# sensor_board_v0_4.net
KiCad netlist of a schematic drawn in EAGLE
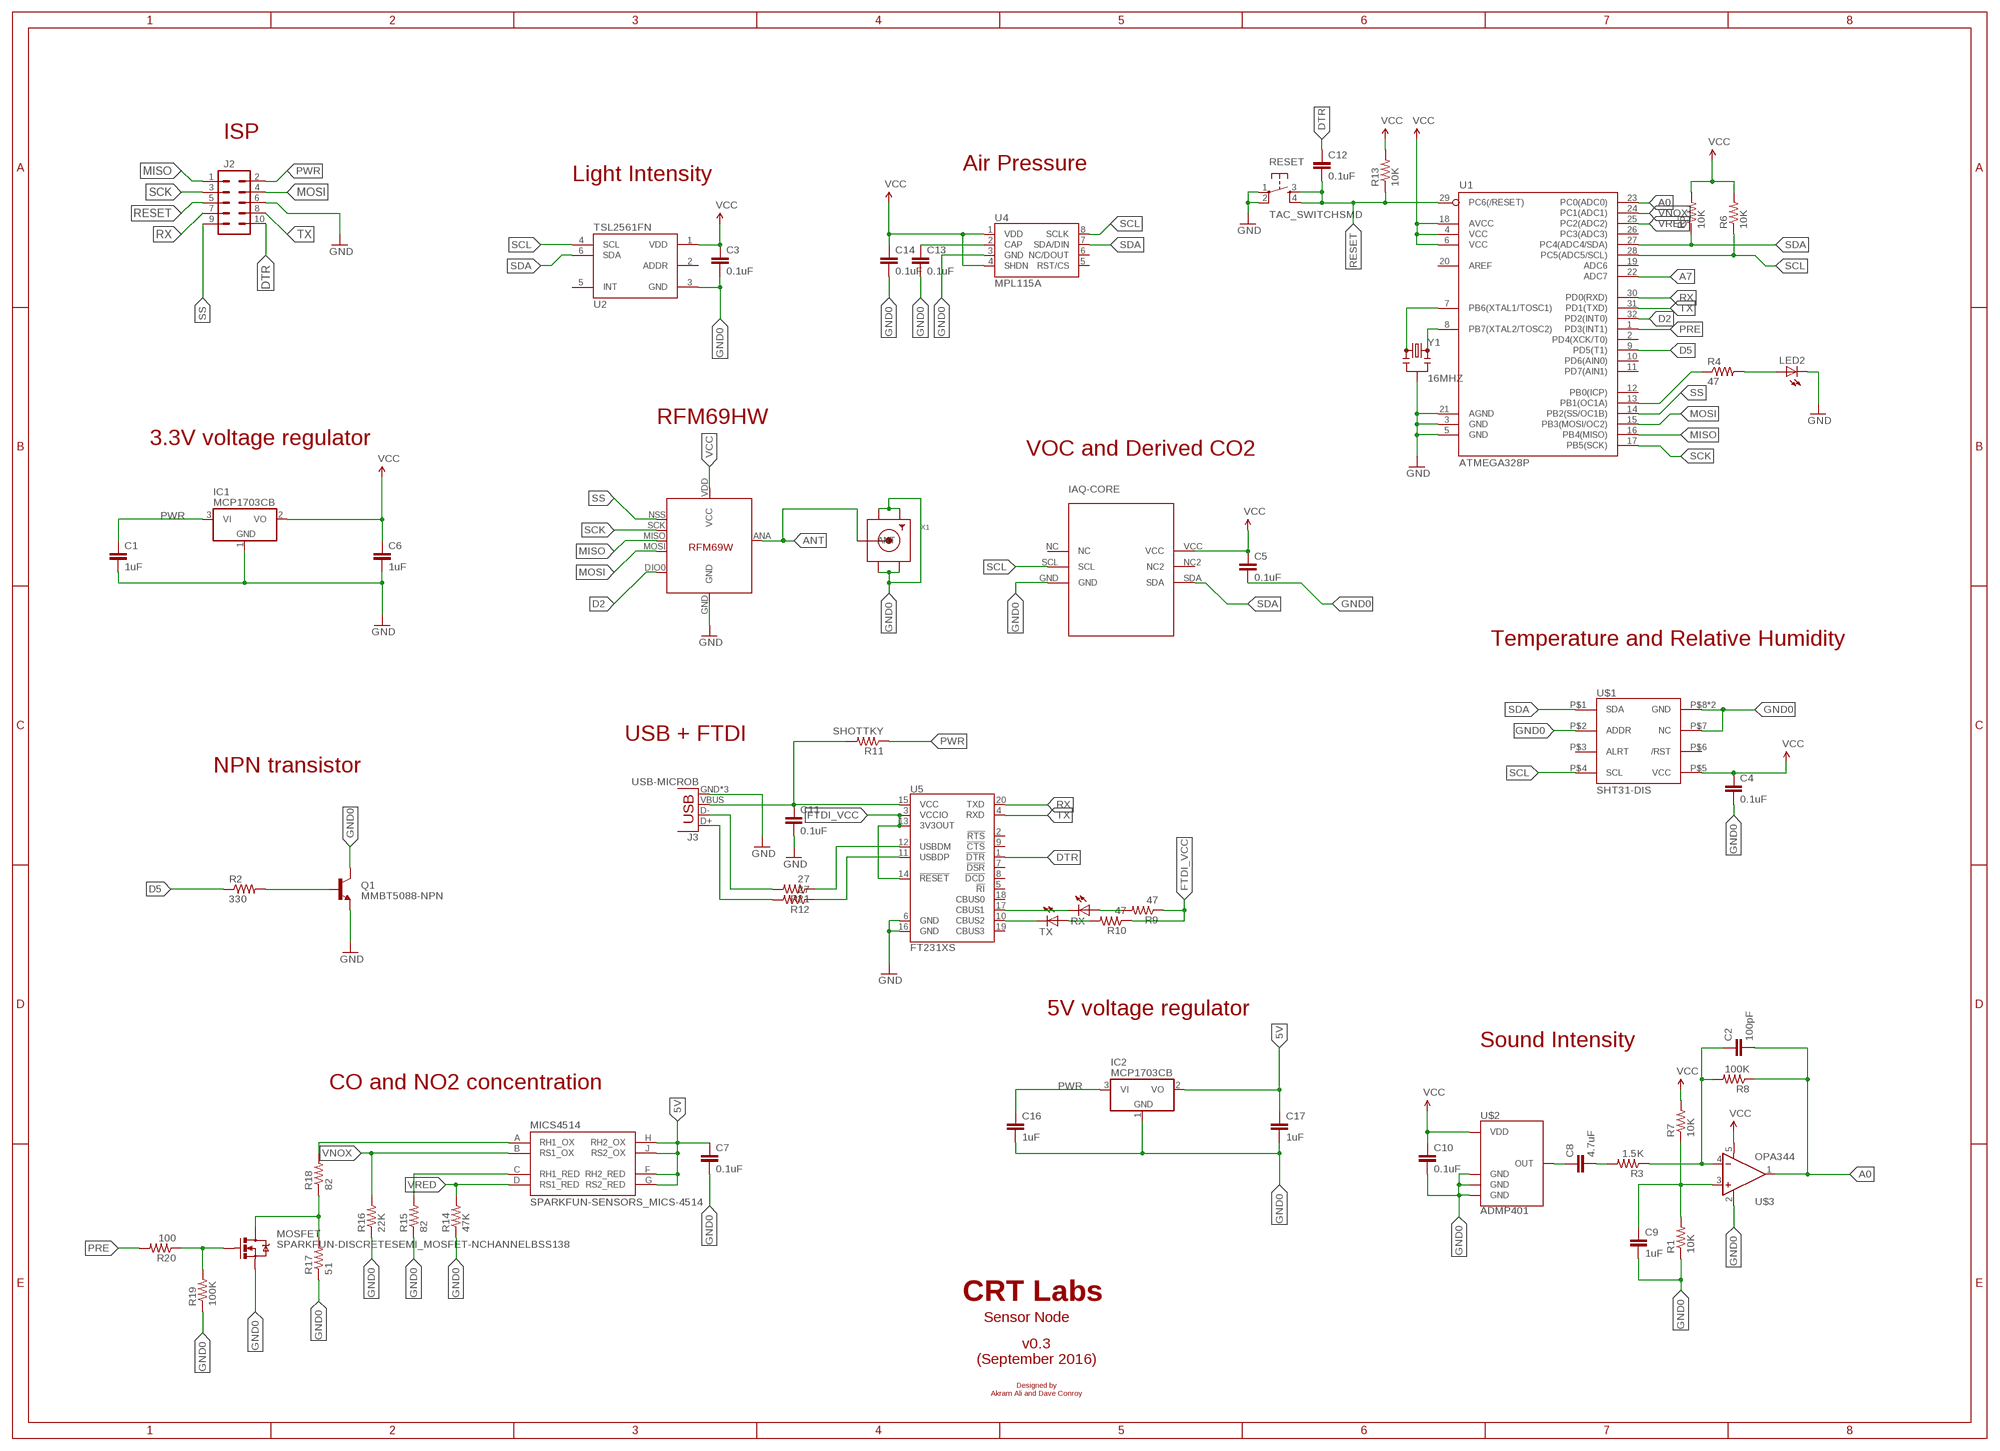
[diagram p0: schematic, sheet 1]

(export (version "E")
  (design (tool "Eeschema 10.0.6"))
  (components
    (comp (ref "C1")
      (value "1uF")
      (footprint "eagle-import:0805")
      (libsource (lib "eagle-import") (part "CAP0805"))
    )
    (comp (ref "C2")
      (value "100pF")
      (footprint "eagle-import:0805")
      (libsource (lib "eagle-import") (part "CAP0805"))
    )
    (comp (ref "C3")
      (value "0.1uF")
      (footprint "eagle-import:0805")
      (libsource (lib "eagle-import") (part "SparkFun-Passives_CAP0805"))
    )
    (comp (ref "C4")
      (value "0.1uF")
      (footprint "eagle-import:0805")
      (libsource (lib "eagle-import") (part "SparkFun-Passives_CAP0805"))
    )
    (comp (ref "C5")
      (value "0.1uF")
      (footprint "eagle-import:0805")
      (libsource (lib "eagle-import") (part "SparkFun-Passives_CAP0805"))
    )
    (comp (ref "C6")
      (value "1uF")
      (footprint "eagle-import:0805")
      (libsource (lib "eagle-import") (part "CAP0805"))
    )
    (comp (ref "C7")
      (value "0.1uF")
      (footprint "eagle-import:0805")
      (libsource (lib "eagle-import") (part "SparkFun-Passives_CAP0805"))
    )
    (comp (ref "C8")
      (value "4.7uF")
      (footprint "eagle-import:0805")
      (libsource (lib "eagle-import") (part "CAP0805"))
    )
    (comp (ref "C9")
      (value "1uF")
      (footprint "eagle-import:0805")
      (libsource (lib "eagle-import") (part "CAP0805"))
    )
    (comp (ref "C10")
      (value "0.1uF")
      (footprint "eagle-import:0805")
      (libsource (lib "eagle-import") (part "CAP0805"))
    )
    (comp (ref "C11")
      (value "0.1uF")
      (footprint "eagle-import:0805")
      (libsource (lib "eagle-import") (part "CAP0805"))
    )
    (comp (ref "C12")
      (value "0.1uF")
      (footprint "eagle-import:0805")
      (libsource (lib "eagle-import") (part "SparkFun-Passives_CAP0805"))
    )
    (comp (ref "C13")
      (value "0.1uF")
      (footprint "eagle-import:0805")
      (libsource (lib "eagle-import") (part "SparkFun-Passives_CAP0805"))
    )
    (comp (ref "C14")
      (value "0.1uF")
      (footprint "eagle-import:0805")
      (libsource (lib "eagle-import") (part "SparkFun-Passives_CAP0805"))
    )
    (comp (ref "C16")
      (value "1uF")
      (footprint "eagle-import:0805")
      (libsource (lib "eagle-import") (part "CAP0805"))
    )
    (comp (ref "C17")
      (value "1uF")
      (footprint "eagle-import:0805")
      (libsource (lib "eagle-import") (part "CAP0805"))
    )
    (comp (ref "IAQ-CORE")
      (value "IAQ-CORE")
      (footprint "eagle-import:IAQ-CORE")
      (fields (field (name "MPN") "IAQ CORE"))
      (libsource (lib "eagle-import") (part "IAQ-CORE"))
    )
    (comp (ref "IC1")
      (value "MCP1703CB")
      (footprint "eagle-import:SOT23")
      (fields (field (name "MPN") "MCP1703T-2502E/CB"))
      (libsource (lib "eagle-import") (part "MCP1703CB"))
    )
    (comp (ref "IC2")
      (value "MCP1703CB")
      (footprint "eagle-import:SOT23")
      (fields (field (name "MPN") "MCP1703T-2502E/CB"))
      (libsource (lib "eagle-import") (part "MCP1703CB"))
    )
    (comp (ref "J2")
      (value "M05X2PTH")
      (footprint "eagle-import:AVR_ICSP")
      (libsource (lib "eagle-import") (part "M05X2PTH"))
    )
    (comp (ref "J3")
      (value "USB-MICROB")
      (footprint "eagle-import:USB-MICROB")
      (libsource (lib "eagle-import") (part "USB-MICROB"))
    )
    (comp (ref "LED2")
      (value "LEDCHIPLED_0805")
      (footprint "eagle-import:CHIPLED_0805")
      (libsource (lib "eagle-import") (part "LEDCHIPLED_0805"))
    )
    (comp (ref "MICS4514")
      (value "SPARKFUN-SENSORS_MICS-4514")
      (footprint "eagle-import:SPARKFUN-SENSORS_MICS_10-SMD")
      (libsource (lib "eagle-import") (part "SPARKFUN-SENSORS_MICS-4514"))
    )
    (comp (ref "MOSFET")
      (value "SPARKFUN-DISCRETESEMI_MOSFET-NCHANNELBSS138")
      (footprint "eagle-import:SPARKFUN-DISCRETESEMI_SOT23-3")
      (libsource (lib "eagle-import") (part "SPARKFUN-DISCRETESEMI_MOSFET-NCHANNELBSS138"))
    )
    (comp (ref "Q1")
      (value "MMBT5088-NPN")
      (footprint "eagle-import:SOT23-3")
      (libsource (lib "eagle-import") (part "TRANSISTOR_NPNMMBT5088"))
    )
    (comp (ref "R1")
      (value "10K")
      (footprint "eagle-import:0805")
      (libsource (lib "eagle-import") (part "RESISTOR0805-RES"))
    )
    (comp (ref "R2")
      (value "330")
      (footprint "eagle-import:0805")
      (libsource (lib "eagle-import") (part "RESISTOR0805-RES"))
    )
    (comp (ref "R3")
      (value "1.5K")
      (footprint "eagle-import:0805")
      (libsource (lib "eagle-import") (part "RESISTOR0805-RES"))
    )
    (comp (ref "R4")
      (value "47")
      (footprint "eagle-import:0805")
      (libsource (lib "eagle-import") (part "SparkFun-Resistors_RESISTOR0805-RES"))
    )
    (comp (ref "R5")
      (value "10K")
      (footprint "eagle-import:0805")
      (libsource (lib "eagle-import") (part "SparkFun-Resistors_RESISTOR0805-RES"))
    )
    (comp (ref "R6")
      (value "10K")
      (footprint "eagle-import:0805")
      (libsource (lib "eagle-import") (part "SparkFun-Resistors_RESISTOR0805-RES"))
    )
    (comp (ref "R7")
      (value "10K")
      (footprint "eagle-import:0805")
      (libsource (lib "eagle-import") (part "RESISTOR0805-RES"))
    )
    (comp (ref "R8")
      (value "100K")
      (footprint "eagle-import:0805")
      (libsource (lib "eagle-import") (part "RESISTOR0805-RES"))
    )
    (comp (ref "R9")
      (value "47")
      (footprint "eagle-import:0805")
      (libsource (lib "eagle-import") (part "RESISTOR0805-RES"))
    )
    (comp (ref "R10")
      (value "47")
      (footprint "eagle-import:0805")
      (libsource (lib "eagle-import") (part "RESISTOR0805-RES"))
    )
    (comp (ref "R11")
      (value "SHOTTKY")
      (footprint "eagle-import:0805")
      (libsource (lib "eagle-import") (part "RESISTOR0805-RES"))
    )
    (comp (ref "R12")
      (value "27")
      (footprint "eagle-import:0805")
      (libsource (lib "eagle-import") (part "RESISTOR0805-RES"))
    )
    (comp (ref "R13")
      (value "10K")
      (footprint "eagle-import:0805")
      (libsource (lib "eagle-import") (part "RESISTOR0805-RES"))
    )
    (comp (ref "R14")
      (value "47K")
      (footprint "eagle-import:0805")
      (libsource (lib "eagle-import") (part "RESISTOR0805-RES"))
    )
    (comp (ref "R15")
      (value "82")
      (footprint "eagle-import:0805")
      (libsource (lib "eagle-import") (part "RESISTOR0805-RES"))
    )
    (comp (ref "R16")
      (value "22K")
      (footprint "eagle-import:0805")
      (libsource (lib "eagle-import") (part "RESISTOR0805-RES"))
    )
    (comp (ref "R17")
      (value "51")
      (footprint "eagle-import:0805")
      (libsource (lib "eagle-import") (part "RESISTOR0805-RES"))
    )
    (comp (ref "R18")
      (value "82")
      (footprint "eagle-import:0805")
      (libsource (lib "eagle-import") (part "RESISTOR0805-RES"))
    )
    (comp (ref "R19")
      (value "100K")
      (footprint "eagle-import:0805")
      (libsource (lib "eagle-import") (part "RESISTOR0805-RES"))
    )
    (comp (ref "R20")
      (value "100")
      (footprint "eagle-import:0805")
      (libsource (lib "eagle-import") (part "RESISTOR0805-RES"))
    )
    (comp (ref "R21")
      (value "27")
      (footprint "eagle-import:0805")
      (libsource (lib "eagle-import") (part "RESISTOR0805-RES"))
    )
    (comp (ref "RESET")
      (value "TAC_SWITCHSMD")
      (footprint "eagle-import:TACTILE-SWITCH-SMD")
      (libsource (lib "eagle-import") (part "TAC_SWITCHSMD"))
    )
    (comp (ref "RX")
      (value "LEDCHIPLED_0805")
      (footprint "eagle-import:CHIPLED_0805")
      (libsource (lib "eagle-import") (part "LEDCHIPLED_0805"))
    )
    (comp (ref "TX")
      (value "LEDCHIPLED_0805")
      (footprint "eagle-import:CHIPLED_0805")
      (libsource (lib "eagle-import") (part "LEDCHIPLED_0805"))
    )
    (comp (ref "U$1")
      (value "SHT31-DIS")
      (footprint "eagle-import:SHT3X")
      (fields (field (name "MPN") "SHT31-DIS-B"))
      (libsource (lib "eagle-import") (part "SHT31-DIS"))
    )
    (comp (ref "U$2")
      (value "ADMP401")
      (footprint "eagle-import:ADMP401")
      (libsource (lib "eagle-import") (part "ADMP401"))
    )
    (comp (ref "U$3")
      (value "OPA344")
      (footprint "eagle-import:SOT23-5")
      (libsource (lib "eagle-import") (part "OPA344"))
    )
    (comp (ref "U$4")
      (value "RFM69HW")
      (footprint "eagle-import:LOWPOWERLAB_RFM69W-MINPADS")
      (libsource (lib "eagle-import") (part "LOWPOWERLAB_RFM69"))
    )
    (comp (ref "U1")
      (value "ATMEGA328P")
      (footprint "eagle-import:TQFP32-08")
      (fields (field (name "MPN") "ATMEGA328PB-AU"))
      (libsource (lib "eagle-import") (part "ATMEGA328P_TQFP"))
    )
    (comp (ref "U2")
      (value "TSL2561FN")
      (footprint "eagle-import:FN-6")
      (fields (field (name "MANF") "AMS-TAOS-USA-Inc."))
      (libsource (lib "eagle-import") (part "TSL2561FN"))
    )
    (comp (ref "U4")
      (value "MPL115A")
      (footprint "eagle-import:LGA8")
      (libsource (lib "eagle-import") (part "MPL115A"))
    )
    (comp (ref "U5")
      (value "FT231XS")
      (footprint "eagle-import:SSOP20_L")
      (libsource (lib "eagle-import") (part "FT231XS"))
    )
    (comp (ref "X1")
      (value "SMACONNECTOR_EDGE")
      (footprint "eagle-import:SMA_EDGELAUNCH")
      (libsource (lib "eagle-import") (part "SMACONNECTOR_EDGE"))
    )
    (comp (ref "Y1")
      (value "16MHZ")
      (footprint "eagle-import:RESONATOR-SMD")
      (libsource (lib "eagle-import") (part "RESONATOR16MHZ"))
    )
  )
  (nets
    (net (code "1") (name "5V") (class "Default")
      (node (ref "C17") (pin "1") (pinfunction "1_1") (pintype "passive"))
      (node (ref "C7") (pin "1") (pinfunction "1_1") (pintype "passive"))
      (node (ref "IC2") (pin "2") (pinfunction "VO_2") (pintype "passive"))
      (node (ref "MICS4514") (pin "F") (pinfunction "RH2_RED_F") (pintype "bidirectional"))
      (node (ref "MICS4514") (pin "G") (pinfunction "RS2_RED_G") (pintype "bidirectional"))
      (node (ref "MICS4514") (pin "H") (pinfunction "RH2_OX_H") (pintype "bidirectional"))
      (node (ref "MICS4514") (pin "J") (pinfunction "RS2_OX_J") (pintype "bidirectional"))
    )
    (net (code "2") (name "A0") (class "Default")
      (node (ref "C2") (pin "2") (pinfunction "2_2") (pintype "passive"))
      (node (ref "R8") (pin "1") (pinfunction "1_1") (pintype "passive"))
      (node (ref "U$3") (pin "1") (pinfunction "OUT_1") (pintype "output"))
      (node (ref "U1") (pin "23") (pinfunction "PC0(ADC0)_23") (pintype "bidirectional"))
    )
    (net (code "3") (name "A7") (class "Default")
      (node (ref "U1") (pin "22") (pinfunction "ADC7_22") (pintype "bidirectional"))
    )
    (net (code "4") (name "ANT") (class "Default")
      (node (ref "U$4") (pin "ANA") (pinfunction "ANT_ANA") (pintype "passive"))
      (node (ref "X1") (pin "P") (pinfunction "ANT_P") (pintype "bidirectional"))
    )
    (net (code "5") (name "D2") (class "Default")
      (node (ref "U$4") (pin "DIO0") (pinfunction "DIO0_DIO0") (pintype "open_collector"))
      (node (ref "U1") (pin "32") (pinfunction "PD2(INT0)_32") (pintype "bidirectional"))
    )
    (net (code "6") (name "D5") (class "Default")
      (node (ref "R2") (pin "1") (pinfunction "1_1") (pintype "passive"))
      (node (ref "U1") (pin "9") (pinfunction "PD5(T1)_9") (pintype "bidirectional"))
    )
    (net (code "7") (name "DTR") (class "Default")
      (node (ref "C12") (pin "1") (pinfunction "1_1") (pintype "passive"))
      (node (ref "J2") (pin "10") (pinfunction "10_10") (pintype "passive"))
      (node (ref "U5") (pin "1") (pinfunction "~{DTR}_1") (pintype "bidirectional"))
    )
    (net (code "8") (name "FTDI_VCC") (class "Default")
      (node (ref "R10") (pin "1") (pinfunction "1_1") (pintype "passive"))
      (node (ref "R9") (pin "1") (pinfunction "1_1") (pintype "passive"))
      (node (ref "U5") (pin "13") (pinfunction "3V3OUT_13") (pintype "bidirectional"))
      (node (ref "U5") (pin "14") (pinfunction "~{RESET}_14") (pintype "bidirectional"))
      (node (ref "U5") (pin "3") (pinfunction "VCCIO_3") (pintype "bidirectional"))
    )
    (net (code "9") (name "GND") (class "Default")
      (node (ref "C1") (pin "2") (pinfunction "2_2") (pintype "passive"))
      (node (ref "C11") (pin "2") (pinfunction "2_2") (pintype "passive"))
      (node (ref "C6") (pin "2") (pinfunction "2_2") (pintype "passive"))
      (node (ref "IC1") (pin "1") (pinfunction "GND_1") (pintype "passive"))
      (node (ref "J2") (pin "6") (pinfunction "6_6") (pintype "passive"))
      (node (ref "J3") (pin "GND") (pinfunction "GND_GND") (pintype "bidirectional"))
      (node (ref "J3") (pin "MT1") (pinfunction "GND_MT1") (pintype "bidirectional"))
      (node (ref "J3") (pin "MT2") (pinfunction "GND_MT2") (pintype "bidirectional"))
      (node (ref "LED2") (pin "C") (pinfunction "C_C") (pintype "passive"))
      (node (ref "Q1") (pin "2") (pinfunction "E_2") (pintype "passive"))
      (node (ref "RESET") (pin "1") (pinfunction "1_1") (pintype "passive"))
      (node (ref "RESET") (pin "2") (pinfunction "2_2") (pintype "passive"))
      (node (ref "U$4") (pin "GND") (pinfunction "GND_GND") (pintype "power_in"))
      (node (ref "U1") (pin "21") (pinfunction "AGND_21") (pintype "bidirectional"))
      (node (ref "U1") (pin "3") (pinfunction "GND_3") (pintype "bidirectional"))
      (node (ref "U1") (pin "5") (pinfunction "GND_5") (pintype "bidirectional"))
      (node (ref "U5") (pin "16") (pinfunction "GND_16") (pintype "bidirectional"))
      (node (ref "U5") (pin "6") (pinfunction "GND_6") (pintype "bidirectional"))
      (node (ref "Y1") (pin "2") (pinfunction "2_2") (pintype "passive"))
    )
    (net (code "10") (name "GND0") (class "Default")
      (node (ref "C10") (pin "2") (pinfunction "2_2") (pintype "passive"))
      (node (ref "C13") (pin "2") (pinfunction "2_2") (pintype "passive"))
      (node (ref "C14") (pin "2") (pinfunction "2_2") (pintype "passive"))
      (node (ref "C16") (pin "2") (pinfunction "2_2") (pintype "passive"))
      (node (ref "C17") (pin "2") (pinfunction "2_2") (pintype "passive"))
      (node (ref "C3") (pin "2") (pinfunction "2_2") (pintype "passive"))
      (node (ref "C4") (pin "2") (pinfunction "2_2") (pintype "passive"))
      (node (ref "C5") (pin "2") (pinfunction "2_2") (pintype "passive"))
      (node (ref "C7") (pin "2") (pinfunction "2_2") (pintype "passive"))
      (node (ref "C9") (pin "2") (pinfunction "2_2") (pintype "passive"))
      (node (ref "IAQ-CORE") (pin "GND") (pinfunction "GND_GND") (pintype "bidirectional"))
      (node (ref "IC2") (pin "1") (pinfunction "GND_1") (pintype "passive"))
      (node (ref "MOSFET") (pin "2") (pinfunction "S_2") (pintype "passive"))
      (node (ref "Q1") (pin "3") (pinfunction "C_3") (pintype "passive"))
      (node (ref "R1") (pin "1") (pinfunction "1_1") (pintype "passive"))
      (node (ref "R14") (pin "1") (pinfunction "1_1") (pintype "passive"))
      (node (ref "R15") (pin "1") (pinfunction "1_1") (pintype "passive"))
      (node (ref "R16") (pin "1") (pinfunction "1_1") (pintype "passive"))
      (node (ref "R17") (pin "1") (pinfunction "1_1") (pintype "passive"))
      (node (ref "R19") (pin "1") (pinfunction "1_1") (pintype "passive"))
      (node (ref "U$1") (pin "P$2") (pinfunction "ADDR_P$2") (pintype "bidirectional"))
      (node (ref "U$1") (pin "P$7") (pinfunction "NC_P$7") (pintype "bidirectional"))
      (node (ref "U$1") (pin "P$8") (pinfunction "GND_P$8") (pintype "bidirectional"))
      (node (ref "U$1") (pin "PAD") (pinfunction "GND_PAD") (pintype "bidirectional"))
      (node (ref "U$2") (pin "2") (pinfunction "GND_2") (pintype "bidirectional"))
      (node (ref "U$2") (pin "4") (pinfunction "GND_4") (pintype "bidirectional"))
      (node (ref "U$2") (pin "6") (pinfunction "GND_6") (pintype "bidirectional"))
      (node (ref "U$3") (pin "2") (pinfunction "V-_2") (pintype "power_in"))
      (node (ref "U2") (pin "3") (pinfunction "GND_3") (pintype "power_in"))
      (node (ref "U4") (pin "3") (pinfunction "GND_3") (pintype "bidirectional"))
      (node (ref "X1") (pin "GND@1") (pinfunction "GND4_GND@1") (pintype "power_in"))
      (node (ref "X1") (pin "GND@2") (pinfunction "GND3_GND@2") (pintype "power_in"))
      (node (ref "X1") (pin "GND@3") (pinfunction "GND2_GND@3") (pintype "power_in"))
      (node (ref "X1") (pin "GND@4") (pinfunction "GND1_GND@4") (pintype "power_in"))
    )
    (net (code "11") (name "MISO") (class "Default")
      (node (ref "J2") (pin "1") (pinfunction "1_1") (pintype "passive"))
      (node (ref "U$4") (pin "MISO") (pinfunction "MISO_MISO") (pintype "input"))
      (node (ref "U1") (pin "16") (pinfunction "PB4(MISO)_16") (pintype "bidirectional"))
    )
    (net (code "12") (name "MOSI") (class "Default")
      (node (ref "J2") (pin "4") (pinfunction "4_4") (pintype "passive"))
      (node (ref "U$4") (pin "MOSI") (pinfunction "MOSI_MOSI") (pintype "output"))
      (node (ref "U1") (pin "15") (pinfunction "PB3(MOSI/OC2)_15") (pintype "bidirectional"))
    )
    (net (code "13") (name "Net-(C8-Pad2)") (class "Default")
      (node (ref "C8") (pin "2") (pinfunction "2_2") (pintype "passive"))
      (node (ref "R3") (pin "2") (pinfunction "2_2") (pintype "passive"))
    )
    (net (code "14") (name "Net-(J3-PadD+)") (class "Default")
      (node (ref "J3") (pin "D+") (pinfunction "D+_D+") (pintype "bidirectional"))
      (node (ref "R12") (pin "2") (pinfunction "2_2") (pintype "passive"))
    )
    (net (code "15") (name "Net-(J3-PadD-)") (class "Default")
      (node (ref "J3") (pin "D-") (pinfunction "D-_D-") (pintype "bidirectional"))
      (node (ref "R21") (pin "2") (pinfunction "2_2") (pintype "passive"))
    )
    (net (code "16") (name "Net-(LED2-PadA)") (class "Default")
      (node (ref "LED2") (pin "A") (pinfunction "A_A") (pintype "passive"))
      (node (ref "R4") (pin "2") (pinfunction "2_2") (pintype "passive"))
    )
    (net (code "17") (name "Net-(MICS4514-RH1_OX)") (class "Default")
      (node (ref "MICS4514") (pin "A") (pinfunction "RH1_OX_A") (pintype "bidirectional"))
      (node (ref "R18") (pin "2") (pinfunction "2_2") (pintype "passive"))
    )
    (net (code "18") (name "Net-(MICS4514-RH1_RED)") (class "Default")
      (node (ref "MICS4514") (pin "C") (pinfunction "RH1_RED_C") (pintype "bidirectional"))
      (node (ref "R15") (pin "2") (pinfunction "2_2") (pintype "passive"))
    )
    (net (code "19") (name "Net-(MOSFET-D)") (class "Default")
      (node (ref "MOSFET") (pin "3") (pinfunction "D_3") (pintype "passive"))
      (node (ref "R17") (pin "2") (pinfunction "2_2") (pintype "passive"))
      (node (ref "R18") (pin "1") (pinfunction "1_1") (pintype "passive"))
    )
    (net (code "20") (name "Net-(MOSFET-G)") (class "Default")
      (node (ref "MOSFET") (pin "1") (pinfunction "G_1") (pintype "passive"))
      (node (ref "R19") (pin "2") (pinfunction "2_2") (pintype "passive"))
      (node (ref "R20") (pin "1") (pinfunction "1_1") (pintype "passive"))
    )
    (net (code "21") (name "Net-(Q1-B)") (class "Default")
      (node (ref "Q1") (pin "1") (pinfunction "B_1") (pintype "passive"))
      (node (ref "R2") (pin "2") (pinfunction "2_2") (pintype "passive"))
    )
    (net (code "22") (name "Net-(R9-Pad2)") (class "Default")
      (node (ref "R9") (pin "2") (pinfunction "2_2") (pintype "passive"))
      (node (ref "RX") (pin "A") (pinfunction "A_A") (pintype "passive"))
    )
    (net (code "23") (name "Net-(R10-Pad2)") (class "Default")
      (node (ref "R10") (pin "2") (pinfunction "2_2") (pintype "passive"))
      (node (ref "TX") (pin "A") (pinfunction "A_A") (pintype "passive"))
    )
    (net (code "24") (name "Net-(U$2-OUT)") (class "Default")
      (node (ref "C8") (pin "1") (pinfunction "1_1") (pintype "passive"))
      (node (ref "U$2") (pin "1") (pinfunction "OUT_1") (pintype "bidirectional"))
    )
    (net (code "25") (name "Net-(U$3-+IN)") (class "Default")
      (node (ref "C9") (pin "1") (pinfunction "1_1") (pintype "passive"))
      (node (ref "R1") (pin "2") (pinfunction "2_2") (pintype "passive"))
      (node (ref "R7") (pin "1") (pinfunction "1_1") (pintype "passive"))
      (node (ref "U$3") (pin "3") (pinfunction "+IN_3") (pintype "input"))
    )
    (net (code "26") (name "Net-(U$3--IN)") (class "Default")
      (node (ref "C2") (pin "1") (pinfunction "1_1") (pintype "passive"))
      (node (ref "R3") (pin "1") (pinfunction "1_1") (pintype "passive"))
      (node (ref "R8") (pin "2") (pinfunction "2_2") (pintype "passive"))
      (node (ref "U$3") (pin "4") (pinfunction "-IN_4") (pintype "input"))
    )
    (net (code "27") (name "Net-(U1-PB1(OC1A))") (class "Default")
      (node (ref "R4") (pin "1") (pinfunction "1_1") (pintype "passive"))
      (node (ref "U1") (pin "13") (pinfunction "PB1(OC1A)_13") (pintype "bidirectional"))
    )
    (net (code "28") (name "Net-(U1-PB6(XTAL1{slash}TOSC1))") (class "Default")
      (node (ref "U1") (pin "7") (pinfunction "PB6(XTAL1/TOSC1)_7") (pintype "bidirectional"))
      (node (ref "Y1") (pin "1") (pinfunction "1_1") (pintype "passive"))
    )
    (net (code "29") (name "Net-(U1-PB7(XTAL2{slash}TOSC2))") (class "Default")
      (node (ref "U1") (pin "8") (pinfunction "PB7(XTAL2/TOSC2)_8") (pintype "bidirectional"))
      (node (ref "Y1") (pin "3") (pinfunction "3_3") (pintype "passive"))
    )
    (net (code "30") (name "Net-(U4-CAP)") (class "Default")
      (node (ref "C13") (pin "1") (pinfunction "1_1") (pintype "passive"))
      (node (ref "U4") (pin "2") (pinfunction "CAP_2") (pintype "bidirectional"))
    )
    (net (code "31") (name "Net-(U5-CBUS1)") (class "Default")
      (node (ref "RX") (pin "C") (pinfunction "C_C") (pintype "passive"))
      (node (ref "U5") (pin "17") (pinfunction "CBUS1_17") (pintype "bidirectional"))
    )
    (net (code "32") (name "Net-(U5-CBUS2)") (class "Default")
      (node (ref "TX") (pin "C") (pinfunction "C_C") (pintype "passive"))
      (node (ref "U5") (pin "10") (pinfunction "CBUS2_10") (pintype "bidirectional"))
    )
    (net (code "33") (name "Net-(U5-USBDM)") (class "Default")
      (node (ref "R21") (pin "1") (pinfunction "1_1") (pintype "passive"))
      (node (ref "U5") (pin "12") (pinfunction "USBDM_12") (pintype "bidirectional"))
    )
    (net (code "34") (name "Net-(U5-USBDP)") (class "Default")
      (node (ref "R12") (pin "1") (pinfunction "1_1") (pintype "passive"))
      (node (ref "U5") (pin "11") (pinfunction "USBDP_11") (pintype "bidirectional"))
    )
    (net (code "35") (name "Net-(U5-VCC)") (class "Default")
      (node (ref "C11") (pin "1") (pinfunction "1_1") (pintype "passive"))
      (node (ref "J3") (pin "VBUS") (pinfunction "VBUS_VBUS") (pintype "bidirectional"))
      (node (ref "R11") (pin "2") (pinfunction "2_2") (pintype "passive"))
      (node (ref "U5") (pin "15") (pinfunction "VCC_15") (pintype "bidirectional"))
    )
    (net (code "36") (name "PRE") (class "Default")
      (node (ref "R20") (pin "2") (pinfunction "2_2") (pintype "passive"))
      (node (ref "U1") (pin "1") (pinfunction "PD3(INT1)_1") (pintype "bidirectional"))
    )
    (net (code "37") (name "PWR") (class "Default")
      (node (ref "C1") (pin "1") (pinfunction "1_1") (pintype "passive"))
      (node (ref "C16") (pin "1") (pinfunction "1_1") (pintype "passive"))
      (node (ref "IC1") (pin "3") (pinfunction "VI_3") (pintype "input"))
      (node (ref "IC2") (pin "3") (pinfunction "VI_3") (pintype "input"))
      (node (ref "J2") (pin "2") (pinfunction "2_2") (pintype "passive"))
      (node (ref "R11") (pin "1") (pinfunction "1_1") (pintype "passive"))
    )
    (net (code "38") (name "RESET") (class "Default")
      (node (ref "C12") (pin "2") (pinfunction "2_2") (pintype "passive"))
      (node (ref "J2") (pin "5") (pinfunction "5_5") (pintype "passive"))
      (node (ref "R13") (pin "1") (pinfunction "1_1") (pintype "passive"))
      (node (ref "RESET") (pin "3") (pinfunction "3_3") (pintype "passive"))
      (node (ref "RESET") (pin "4") (pinfunction "4_4") (pintype "passive"))
      (node (ref "U1") (pin "29") (pinfunction "PC6(/RESET)_29") (pintype "bidirectional"))
    )
    (net (code "39") (name "RX") (class "Default")
      (node (ref "J2") (pin "7") (pinfunction "7_7") (pintype "passive"))
      (node (ref "U1") (pin "30") (pinfunction "PD0(RXD)_30") (pintype "bidirectional"))
      (node (ref "U5") (pin "20") (pinfunction "TXD_20") (pintype "bidirectional"))
    )
    (net (code "40") (name "SCK") (class "Default")
      (node (ref "J2") (pin "3") (pinfunction "3_3") (pintype "passive"))
      (node (ref "U$4") (pin "SCK") (pinfunction "SCK_SCK") (pintype "input"))
      (node (ref "U1") (pin "17") (pinfunction "PB5(SCK)_17") (pintype "bidirectional"))
    )
    (net (code "41") (name "SCL") (class "Default")
      (node (ref "IAQ-CORE") (pin "SCL") (pinfunction "SCL_SCL") (pintype "bidirectional"))
      (node (ref "R6") (pin "1") (pinfunction "1_1") (pintype "passive"))
      (node (ref "U$1") (pin "P$4") (pinfunction "SCL_P$4") (pintype "bidirectional"))
      (node (ref "U1") (pin "28") (pinfunction "PC5(ADC5/SCL)_28") (pintype "bidirectional"))
      (node (ref "U2") (pin "4") (pinfunction "SCL_4") (pintype "input"))
      (node (ref "U4") (pin "8") (pinfunction "SCLK_8") (pintype "bidirectional"))
    )
    (net (code "42") (name "SDA") (class "Default")
      (node (ref "IAQ-CORE") (pin "SDA") (pinfunction "SDA_SDA") (pintype "bidirectional"))
      (node (ref "R5") (pin "1") (pinfunction "1_1") (pintype "passive"))
      (node (ref "U$1") (pin "P$1") (pinfunction "SDA_P$1") (pintype "bidirectional"))
      (node (ref "U1") (pin "27") (pinfunction "PC4(ADC4/SDA)_27") (pintype "bidirectional"))
      (node (ref "U2") (pin "6") (pinfunction "SDA_6") (pintype "bidirectional"))
      (node (ref "U4") (pin "7") (pinfunction "SDA/DIN_7") (pintype "bidirectional"))
    )
    (net (code "43") (name "SS") (class "Default")
      (node (ref "J2") (pin "9") (pinfunction "9_9") (pintype "passive"))
      (node (ref "U$4") (pin "NSS") (pinfunction "SEL_NSS") (pintype "input"))
      (node (ref "U1") (pin "14") (pinfunction "PB2(SS/OC1B)_14") (pintype "bidirectional"))
    )
    (net (code "44") (name "TX") (class "Default")
      (node (ref "J2") (pin "8") (pinfunction "8_8") (pintype "passive"))
      (node (ref "U1") (pin "31") (pinfunction "PD1(TXD)_31") (pintype "bidirectional"))
      (node (ref "U5") (pin "4") (pinfunction "RXD_4") (pintype "bidirectional"))
    )
    (net (code "45") (name "VCC") (class "Default")
      (node (ref "C10") (pin "1") (pinfunction "1_1") (pintype "passive"))
      (node (ref "C14") (pin "1") (pinfunction "1_1") (pintype "passive"))
      (node (ref "C3") (pin "1") (pinfunction "1_1") (pintype "passive"))
      (node (ref "C4") (pin "1") (pinfunction "1_1") (pintype "passive"))
      (node (ref "C5") (pin "1") (pinfunction "1_1") (pintype "passive"))
      (node (ref "C6") (pin "1") (pinfunction "1_1") (pintype "passive"))
      (node (ref "IAQ-CORE") (pin "VCC") (pinfunction "VCC_VCC") (pintype "bidirectional"))
      (node (ref "IC1") (pin "2") (pinfunction "VO_2") (pintype "passive"))
      (node (ref "R13") (pin "2") (pinfunction "2_2") (pintype "passive"))
      (node (ref "R5") (pin "2") (pinfunction "2_2") (pintype "passive"))
      (node (ref "R6") (pin "2") (pinfunction "2_2") (pintype "passive"))
      (node (ref "R7") (pin "2") (pinfunction "2_2") (pintype "passive"))
      (node (ref "U$1") (pin "P$5") (pinfunction "VCC_P$5") (pintype "bidirectional"))
      (node (ref "U$2") (pin "5") (pinfunction "VDD_5") (pintype "bidirectional"))
      (node (ref "U$3") (pin "5") (pinfunction "V+_5") (pintype "power_in"))
      (node (ref "U$4") (pin "VDD") (pinfunction "VCC_VDD") (pintype "power_in"))
      (node (ref "U1") (pin "18") (pinfunction "AVCC_18") (pintype "bidirectional"))
      (node (ref "U1") (pin "4") (pinfunction "VCC_4") (pintype "bidirectional"))
      (node (ref "U1") (pin "6") (pinfunction "VCC_6") (pintype "bidirectional"))
      (node (ref "U2") (pin "1") (pinfunction "VDD_1") (pintype "power_in"))
      (node (ref "U4") (pin "1") (pinfunction "VDD_1") (pintype "bidirectional"))
      (node (ref "U4") (pin "4") (pinfunction "SHDN_4") (pintype "bidirectional"))
    )
    (net (code "46") (name "VNOX") (class "Default")
      (node (ref "MICS4514") (pin "B") (pinfunction "RS1_OX_B") (pintype "bidirectional"))
      (node (ref "R16") (pin "2") (pinfunction "2_2") (pintype "passive"))
      (node (ref "U1") (pin "24") (pinfunction "PC1(ADC1)_24") (pintype "bidirectional"))
    )
    (net (code "47") (name "VRED") (class "Default")
      (node (ref "MICS4514") (pin "D") (pinfunction "RS1_RED_D") (pintype "bidirectional"))
      (node (ref "R14") (pin "2") (pinfunction "2_2") (pintype "passive"))
      (node (ref "U1") (pin "25") (pinfunction "PC2(ADC2)_25") (pintype "bidirectional"))
    )
    (net (code "48") (name "unconnected-(IAQ-CORE-PadNC)") (class "Default")
      (node (ref "IAQ-CORE") (pin "NC") (pinfunction "NC_NC") (pintype "bidirectional"))
    )
    (net (code "49") (name "unconnected-(IAQ-CORE-PadNC2)") (class "Default")
      (node (ref "IAQ-CORE") (pin "NC2") (pinfunction "NC2_NC2") (pintype "bidirectional"))
    )
    (net (code "50") (name "unconnected-(U$1-ALRT-PadP$3)") (class "Default")
      (node (ref "U$1") (pin "P$3") (pinfunction "ALRT_P$3") (pintype "bidirectional"))
    )
    (net (code "51") (name "unconnected-(U$1-{slash}RST-PadP$6)") (class "Default")
      (node (ref "U$1") (pin "P$6") (pinfunction "/RST_P$6") (pintype "bidirectional"))
    )
    (net (code "52") (name "unconnected-(U1-ADC6-Pad19)") (class "Default")
      (node (ref "U1") (pin "19") (pinfunction "ADC6_19") (pintype "bidirectional"))
    )
    (net (code "53") (name "unconnected-(U1-AREF-Pad20)") (class "Default")
      (node (ref "U1") (pin "20") (pinfunction "AREF_20") (pintype "bidirectional"))
    )
    (net (code "54") (name "unconnected-(U1-PB0(ICP)-Pad12)") (class "Default")
      (node (ref "U1") (pin "12") (pinfunction "PB0(ICP)_12") (pintype "bidirectional"))
    )
    (net (code "55") (name "unconnected-(U1-PC3(ADC3)-Pad26)") (class "Default")
      (node (ref "U1") (pin "26") (pinfunction "PC3(ADC3)_26") (pintype "bidirectional"))
    )
    (net (code "56") (name "unconnected-(U1-PD4(XCK{slash}T0)-Pad2)") (class "Default")
      (node (ref "U1") (pin "2") (pinfunction "PD4(XCK/T0)_2") (pintype "bidirectional"))
    )
    (net (code "57") (name "unconnected-(U1-PD6(AIN0)-Pad10)") (class "Default")
      (node (ref "U1") (pin "10") (pinfunction "PD6(AIN0)_10") (pintype "bidirectional"))
    )
    (net (code "58") (name "unconnected-(U1-PD7(AIN1)-Pad11)") (class "Default")
      (node (ref "U1") (pin "11") (pinfunction "PD7(AIN1)_11") (pintype "bidirectional"))
    )
    (net (code "59") (name "unconnected-(U2-ADDR-Pad2)") (class "Default")
      (node (ref "U2") (pin "2") (pinfunction "ADDR_2") (pintype "input"))
    )
    (net (code "60") (name "unconnected-(U2-INT-Pad5)") (class "Default")
      (node (ref "U2") (pin "5") (pinfunction "INT_5") (pintype "output"))
    )
    (net (code "61") (name "unconnected-(U4-NC{slash}DOUT-Pad6)") (class "Default")
      (node (ref "U4") (pin "6") (pinfunction "NC/DOUT_6") (pintype "bidirectional"))
    )
    (net (code "62") (name "unconnected-(U4-RST{slash}CS-Pad5)") (class "Default")
      (node (ref "U4") (pin "5") (pinfunction "RST/CS_5") (pintype "bidirectional"))
    )
    (net (code "63") (name "unconnected-(U5-CBUS0-Pad18)") (class "Default")
      (node (ref "U5") (pin "18") (pinfunction "CBUS0_18") (pintype "bidirectional"))
    )
    (net (code "64") (name "unconnected-(U5-CBUS3-Pad19)") (class "Default")
      (node (ref "U5") (pin "19") (pinfunction "CBUS3_19") (pintype "bidirectional"))
    )
    (net (code "65") (name "unconnected-(U5-~{CTS}-Pad9)") (class "Default")
      (node (ref "U5") (pin "9") (pinfunction "~{CTS}_9") (pintype "bidirectional"))
    )
    (net (code "66") (name "unconnected-(U5-~{DCD}-Pad8)") (class "Default")
      (node (ref "U5") (pin "8") (pinfunction "~{DCD}_8") (pintype "bidirectional"))
    )
    (net (code "67") (name "unconnected-(U5-~{DSR}-Pad7)") (class "Default")
      (node (ref "U5") (pin "7") (pinfunction "~{DSR}_7") (pintype "bidirectional"))
    )
    (net (code "68") (name "unconnected-(U5-~{RI}-Pad5)") (class "Default")
      (node (ref "U5") (pin "5") (pinfunction "~{RI}_5") (pintype "bidirectional"))
    )
    (net (code "69") (name "unconnected-(U5-~{RTS}-Pad2)") (class "Default")
      (node (ref "U5") (pin "2") (pinfunction "~{RTS}_2") (pintype "bidirectional"))
    )
  )
)
